# voltage_regulator.net
KiCad netlist of a schematic drawn in EAGLE
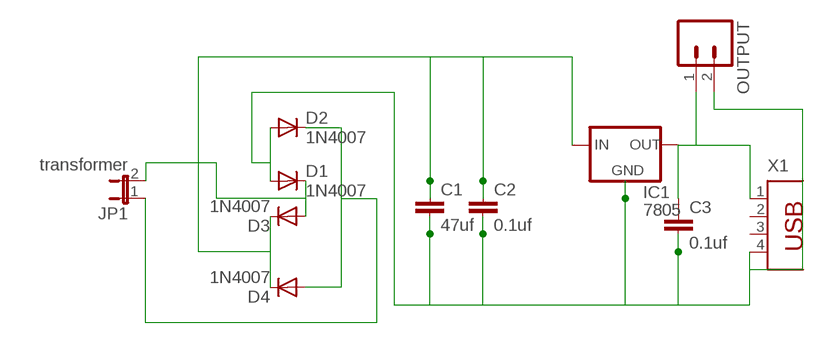
[diagram p0: schematic, sheet 1]

(export (version "E")
  (design (tool "Eeschema 10.0.6"))
  (components
    (comp (ref "C1")
      (value "47uf")
      (footprint "eagle-import:C2.5-3")
      (libsource (lib "eagle-import") (part "C2,5-3"))
    )
    (comp (ref "C2")
      (value "0.1uf")
      (footprint "eagle-import:C2.5-3")
      (libsource (lib "eagle-import") (part "C2,5-3"))
    )
    (comp (ref "C3")
      (value "0.1uf")
      (footprint "eagle-import:C2.5-3")
      (libsource (lib "eagle-import") (part "C2,5-3"))
    )
    (comp (ref "D1")
      (value "1N4007")
      (footprint "eagle-import:DO41-10")
      (libsource (lib "eagle-import") (part "1N4004"))
    )
    (comp (ref "D2")
      (value "1N4007")
      (footprint "eagle-import:DO41-10")
      (libsource (lib "eagle-import") (part "1N4004"))
    )
    (comp (ref "D3")
      (value "1N4007")
      (footprint "eagle-import:DO41-10")
      (libsource (lib "eagle-import") (part "1N4004"))
    )
    (comp (ref "D4")
      (value "1N4007")
      (footprint "eagle-import:DO41-10")
      (libsource (lib "eagle-import") (part "1N4004"))
    )
    (comp (ref "IC1")
      (value "7805")
      (footprint "eagle-import:78XXL")
      (libsource (lib "eagle-import") (part "78XXL"))
    )
    (comp (ref "JP1")
      (value "transformer")
      (footprint "eagle-import:JP1")
      (libsource (lib "eagle-import") (part "JP1E"))
    )
    (comp (ref "OUTPUT")
      (value "M02")
      (footprint "eagle-import:02P")
      (libsource (lib "eagle-import") (part "M02"))
    )
    (comp (ref "X1")
      (value "PN87520")
      (footprint "eagle-import:PN87520")
      (libsource (lib "eagle-import") (part "PN87520"))
    )
  )
  (nets
    (net (code "1") (name "Net-(C1-Pad1)") (class "Default")
      (node (ref "C1") (pin "1") (pinfunction "1_1") (pintype "passive"))
      (node (ref "C2") (pin "1") (pinfunction "1_1") (pintype "passive"))
      (node (ref "D3") (pin "C") (pinfunction "C_C") (pintype "passive"))
      (node (ref "D4") (pin "C") (pinfunction "C_C") (pintype "passive"))
      (node (ref "IC1") (pin "IN") (pinfunction "IN_IN") (pintype "input"))
    )
    (net (code "2") (name "Net-(C1-Pad2)") (class "Default")
      (node (ref "C1") (pin "2") (pinfunction "2_2") (pintype "passive"))
      (node (ref "C2") (pin "2") (pinfunction "2_2") (pintype "passive"))
      (node (ref "C3") (pin "2") (pinfunction "2_2") (pintype "passive"))
      (node (ref "D1") (pin "A") (pinfunction "A_A") (pintype "passive"))
      (node (ref "D2") (pin "A") (pinfunction "A_A") (pintype "passive"))
      (node (ref "IC1") (pin "GND") (pinfunction "GND_GND") (pintype "input"))
      (node (ref "OUTPUT") (pin "2") (pinfunction "2_2") (pintype "passive"))
      (node (ref "X1") (pin "4") (pinfunction "4_4") (pintype "passive"))
    )
    (net (code "3") (name "Net-(C3-Pad1)") (class "Default")
      (node (ref "C3") (pin "1") (pinfunction "1_1") (pintype "passive"))
      (node (ref "IC1") (pin "OUT") (pinfunction "OUT_OUT") (pintype "passive"))
      (node (ref "OUTPUT") (pin "1") (pinfunction "1_1") (pintype "passive"))
      (node (ref "X1") (pin "1") (pinfunction "1_1") (pintype "passive"))
    )
    (net (code "4") (name "Net-(D1-PadC)") (class "Default")
      (node (ref "D1") (pin "C") (pinfunction "C_C") (pintype "passive"))
      (node (ref "D3") (pin "A") (pinfunction "A_A") (pintype "passive"))
      (node (ref "JP1") (pin "2") (pinfunction "2_2") (pintype "passive"))
    )
    (net (code "5") (name "Net-(D2-PadC)") (class "Default")
      (node (ref "D2") (pin "C") (pinfunction "C_C") (pintype "passive"))
      (node (ref "D4") (pin "A") (pinfunction "A_A") (pintype "passive"))
      (node (ref "JP1") (pin "1") (pinfunction "1_1") (pintype "passive"))
    )
    (net (code "6") (name "unconnected-(X1-Pad2)") (class "Default")
      (node (ref "X1") (pin "2") (pinfunction "2_2") (pintype "passive"))
    )
    (net (code "7") (name "unconnected-(X1-Pad3)") (class "Default")
      (node (ref "X1") (pin "3") (pinfunction "3_3") (pintype "passive"))
    )
  )
)
